# 433.net
KiCad netlist of a schematic drawn in EasyEDA Pro
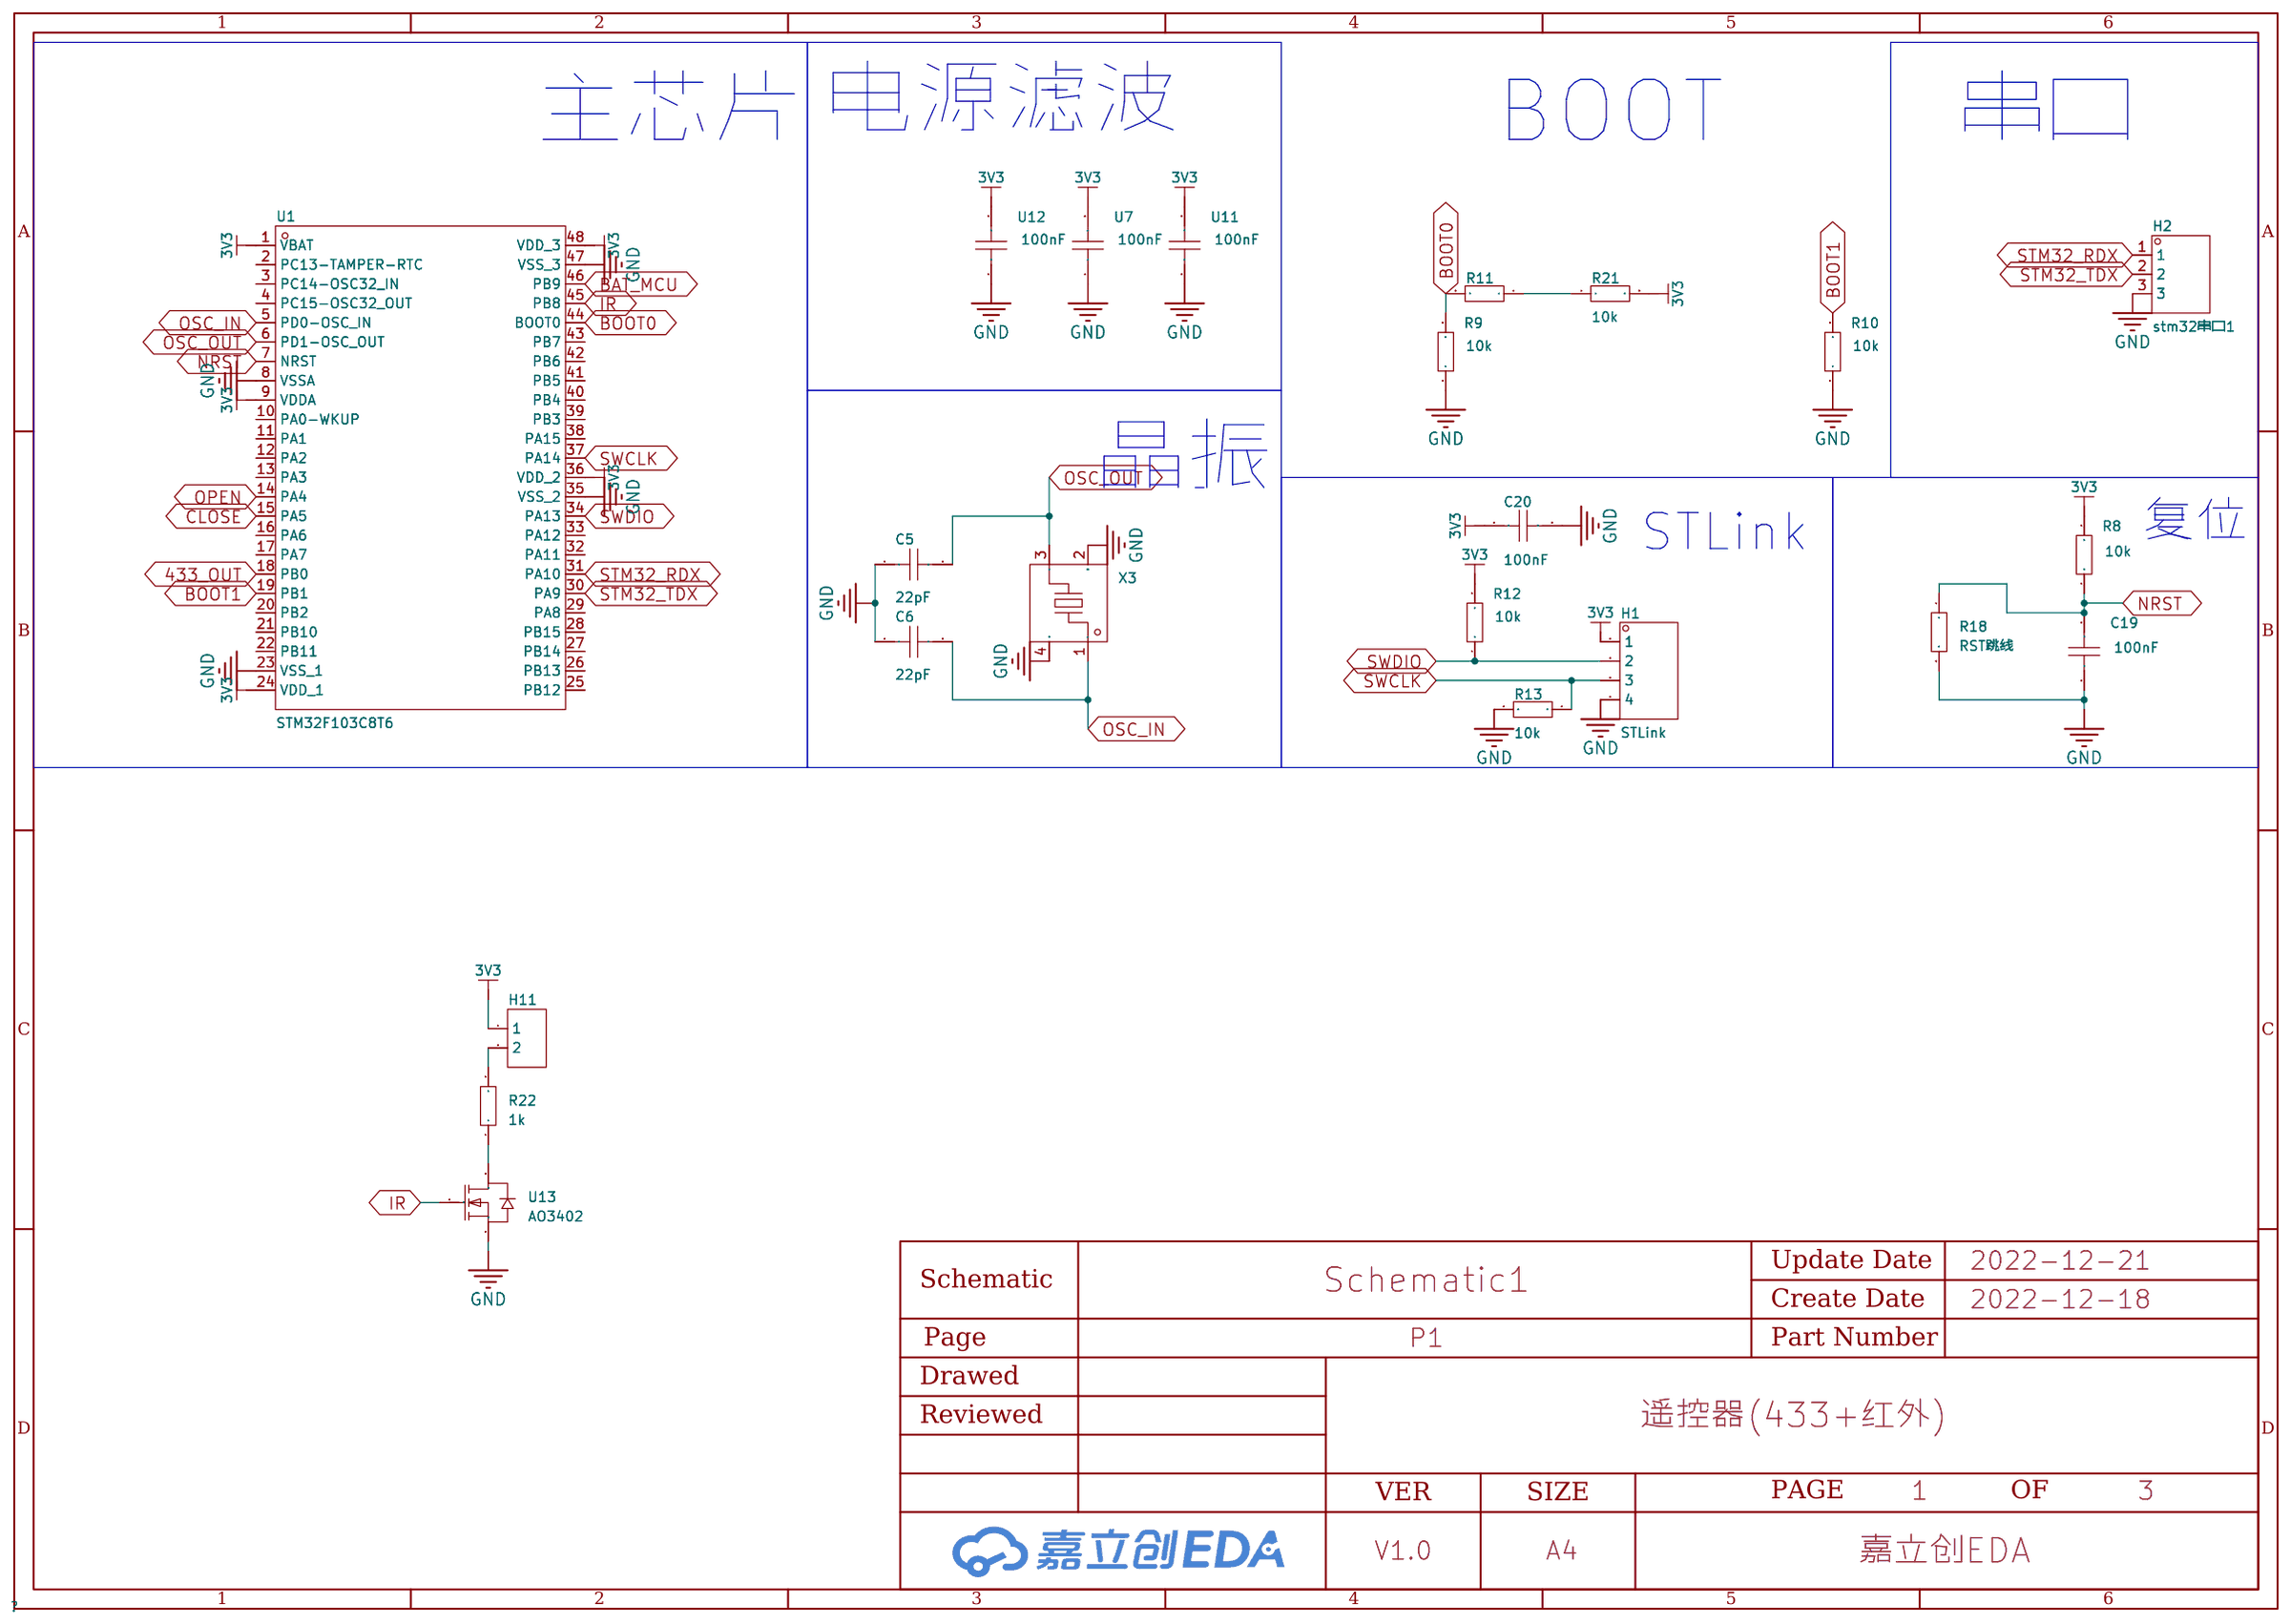
[diagram p0: P1]
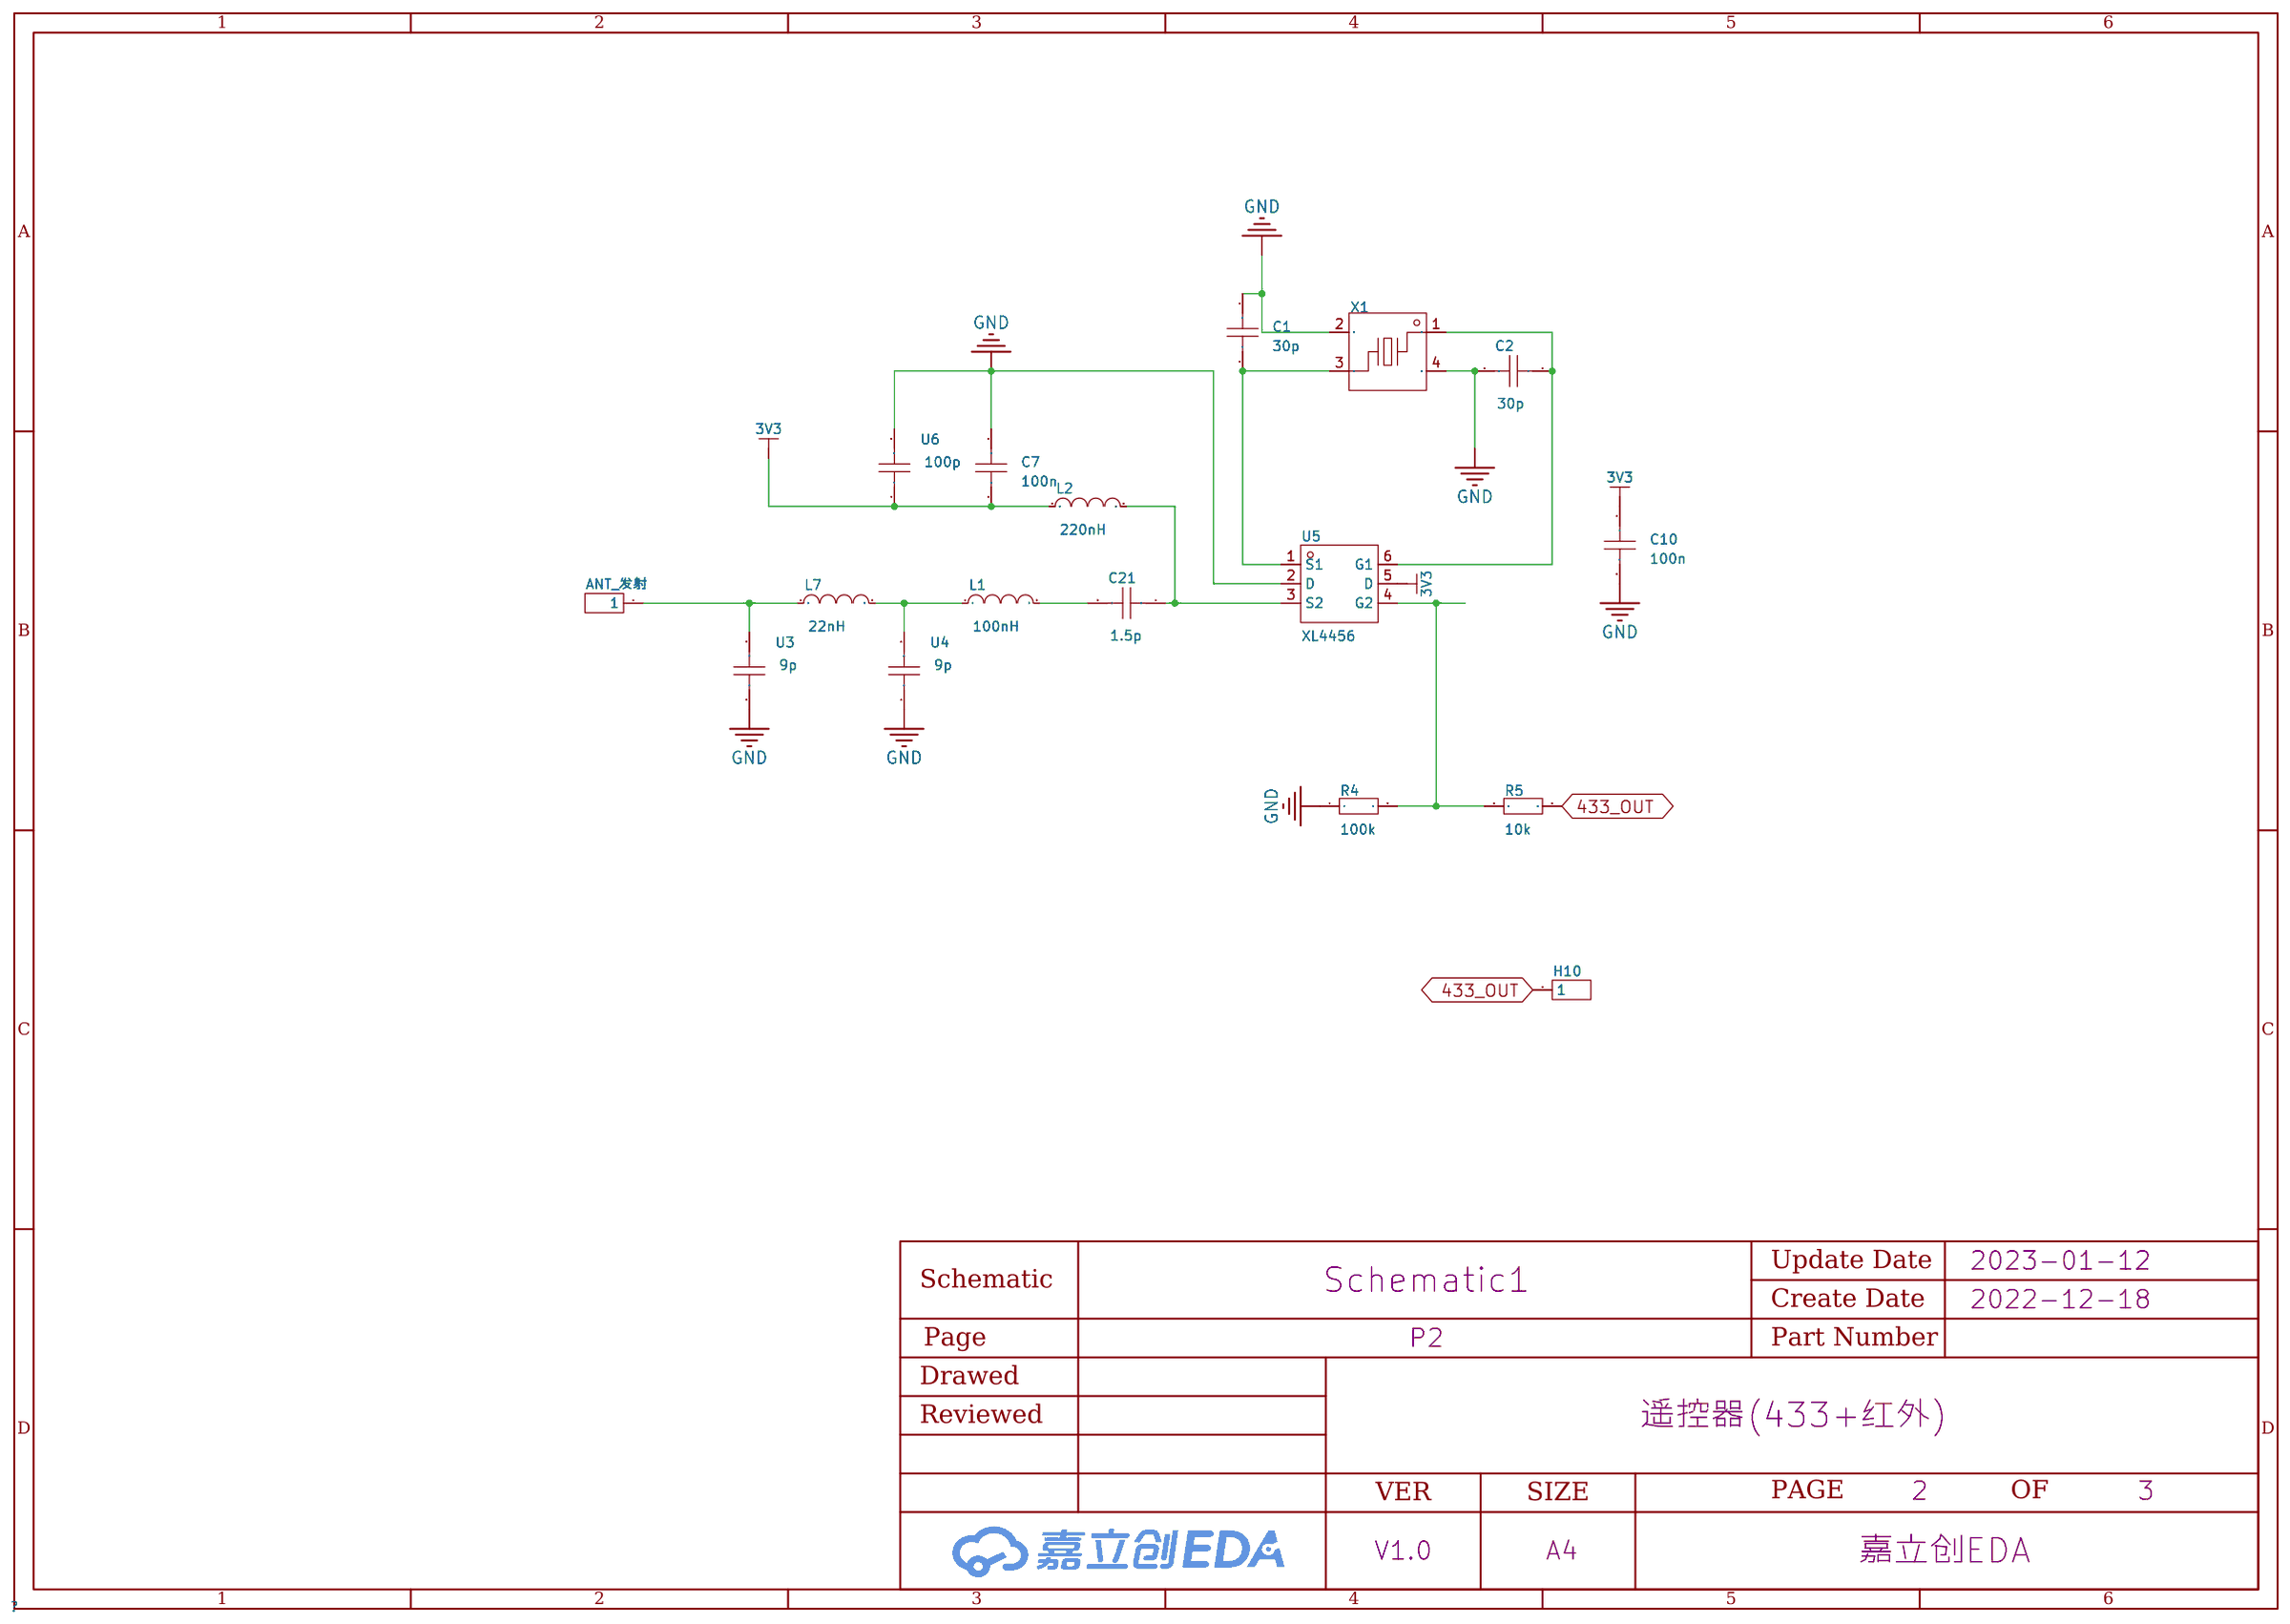
[diagram p1: P2]
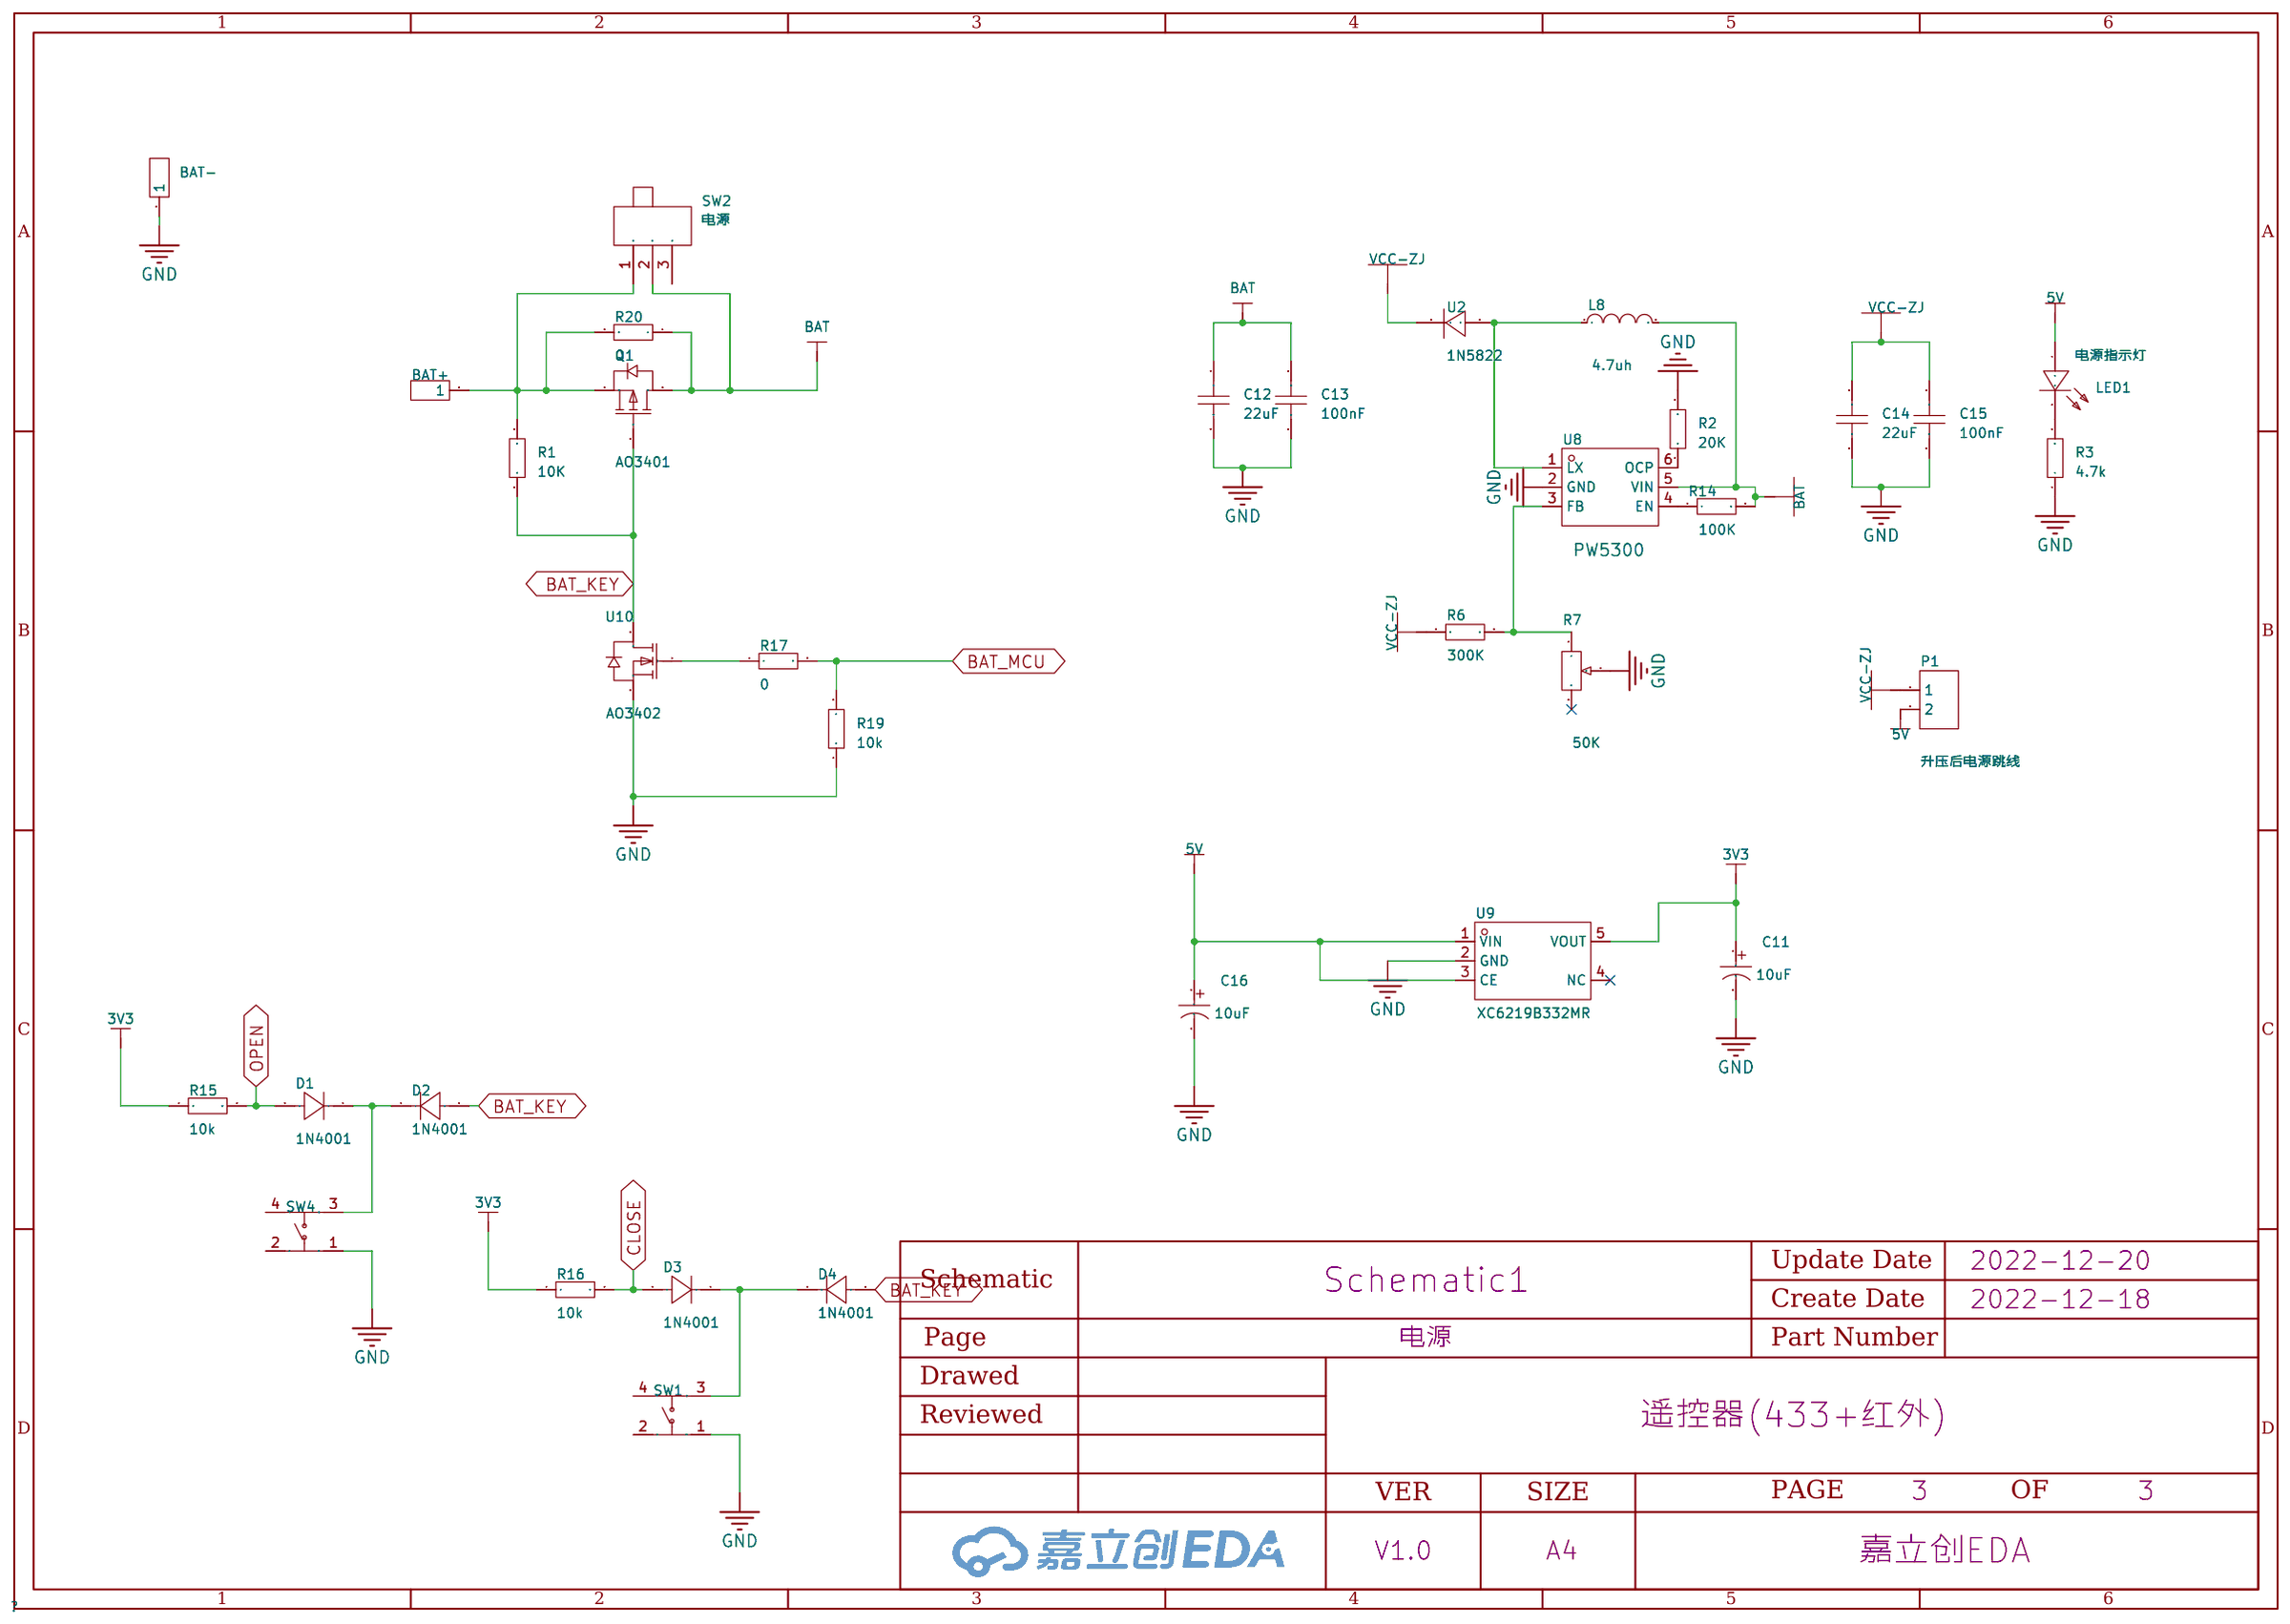
[diagram p2: 电源]

(export (version "E")
  (design (tool "Eeschema 10.0.6"))
  (components
    (comp (ref "C5")
      (value "22pF")
      (footprint "easyedapro:C0805")
      (fields (field (name "Manufacturer Part") "0805"))
      (libsource (lib "easyedapro") (part "0805_C9900012713"))
    )
    (comp (ref "C6")
      (value "22pF")
      (footprint "easyedapro:C0805")
      (fields (field (name "Manufacturer Part") "0805"))
      (libsource (lib "easyedapro") (part "0805_C9900012713"))
    )
    (comp (ref "C19")
      (value "100nF")
      (footprint "easyedapro:C0805")
      (fields (field (name "Manufacturer Part") "0805"))
      (libsource (lib "easyedapro") (part "0805_C9900012713"))
    )
    (comp (ref "C20")
      (value "100nF")
      (footprint "easyedapro:C0805")
      (fields (field (name "Manufacturer Part") "0805"))
      (libsource (lib "easyedapro") (part "0805_C9900012713"))
    )
    (comp (ref "H1")
      (value "STLink")
      (footprint "easyedapro:HDR-TH_4P-P2.54-V-M")
      (fields (field (name "Manufacturer Part") "B-2100S04P-A110") (field (name "Manufacturer") "Ckmtw(灿科盟)"))
      (libsource (lib "easyedapro") (part "Header-Male-2.54_1x4"))
    )
    (comp (ref "H2")
      (value "stm32串口1")
      (footprint "easyedapro:HDR-TH_3P-P2.54-V-M-1")
      (fields (field (name "Manufacturer Part") "77311-102-03LF") (field (name "Manufacturer") "Amphenol"))
      (libsource (lib "easyedapro") (part "77311-102-03LF"))
    )
    (comp (ref "H11")
      (value "~")
      (footprint "easyedapro:HDR-TH_2P-P2.54-V-F")
      (libsource (lib "easyedapro") (part "Header-Female-2.54_1x2"))
    )
    (comp (ref "R8")
      (value "10k")
      (footprint "easyedapro:R0805")
      (fields (field (name "Manufacturer Part") "0805"))
      (libsource (lib "easyedapro") (part "0805"))
    )
    (comp (ref "R9")
      (value "10k")
      (footprint "easyedapro:R0805")
      (fields (field (name "Manufacturer Part") "0805"))
      (libsource (lib "easyedapro") (part "0805"))
    )
    (comp (ref "R10")
      (value "10k")
      (footprint "easyedapro:R0805")
      (fields (field (name "Manufacturer Part") "0805"))
      (libsource (lib "easyedapro") (part "0805"))
    )
    (comp (ref "R11")
      (value "boot0跳线")
      (footprint "easyedapro:R0805")
      (fields (field (name "Manufacturer Part") "0805"))
      (libsource (lib "easyedapro") (part "0805"))
    )
    (comp (ref "R12")
      (value "10k")
      (footprint "easyedapro:R0805")
      (fields (field (name "Manufacturer Part") "0805"))
      (libsource (lib "easyedapro") (part "0805"))
    )
    (comp (ref "R13")
      (value "10k")
      (footprint "easyedapro:R0805")
      (fields (field (name "Manufacturer Part") "0805"))
      (libsource (lib "easyedapro") (part "0805"))
    )
    (comp (ref "R18")
      (value "RST跳线")
      (footprint "easyedapro:R0805")
      (fields (field (name "Manufacturer Part") "0805"))
      (libsource (lib "easyedapro") (part "0805"))
    )
    (comp (ref "R21")
      (value "10k")
      (footprint "easyedapro:R0805")
      (fields (field (name "Manufacturer Part") "0805"))
      (libsource (lib "easyedapro") (part "0805"))
    )
    (comp (ref "R22")
      (value "1k")
      (footprint "easyedapro:R0805")
      (fields (field (name "Manufacturer Part") "0805"))
      (libsource (lib "easyedapro") (part "0805"))
    )
    (comp (ref "U1")
      (value "STM32F103C8T6")
      (footprint "easyedapro:LQFP-48_L7.0-W7.0-P0.50-LS9.0-BL")
      (description "CPU位数:32-Bit;ROM类型:FLASH;CPU内核:ARM® Cortex®-M3;主频（MAX):72MHz;工作电压:2V ~ 3.6V;")
      (fields (field (name "Manufacturer") "ST(意法半导体)"))
      (libsource (lib "easyedapro") (part "STM32F103C8T6"))
    )
    (comp (ref "U7")
      (value "100nF")
      (footprint "easyedapro:C0603")
      (fields (field (name "Manufacturer Part") "1nF-C0603"))
      (libsource (lib "easyedapro") (part "1NF-C0603"))
    )
    (comp (ref "U11")
      (value "100nF")
      (footprint "easyedapro:C0603")
      (fields (field (name "Manufacturer Part") "1nF-C0603"))
      (libsource (lib "easyedapro") (part "1NF-C0603"))
    )
    (comp (ref "U12")
      (value "100nF")
      (footprint "easyedapro:C0603")
      (fields (field (name "Manufacturer Part") "1nF-C0603"))
      (libsource (lib "easyedapro") (part "1NF-C0603"))
    )
    (comp (ref "U13")
      (value "AO3402")
      (footprint "easyedapro:SOT-23-3_L2.9-W1.3-P1.90-LS2.4-BR")
      (fields (field (name "Manufacturer") "BORN(伯恩半导体)"))
      (libsource (lib "easyedapro") (part "AO3402_C5148472"))
    )
    (comp (ref "X3")
      (value "NX3225SA-26MHz-STD-CSR-6")
      (footprint "easyedapro:CRYSTAL-SMD_4P-L3.2-W2.5-BL")
      (fields (field (name "Manufacturer") "NDK"))
      (libsource (lib "easyedapro") (part "NX3225SA-26MHZ-STD-CSR-6"))
    )
    (comp (ref "ANT_发射")
      (value "~")
      (footprint "easyedapro:HDR-TH_1P-V-M_XKB_X4611WV-01I-C28D40")
      (libsource (lib "easyedapro") (part "HDR_1x1"))
    )
    (comp (ref "C1")
      (value "30p")
      (fields (field (name "Manufacturer Part") "0805"))
      (libsource (lib "easyedapro") (part "0805_C9900012713"))
    )
    (comp (ref "C2")
      (value "30p")
      (fields (field (name "Manufacturer Part") "0805"))
      (libsource (lib "easyedapro") (part "0805_C9900012713"))
    )
    (comp (ref "C7")
      (value "100n")
      (fields (field (name "Manufacturer Part") "0805"))
      (libsource (lib "easyedapro") (part "0805_C9900012713"))
    )
    (comp (ref "C10")
      (value "100n")
      (fields (field (name "Manufacturer Part") "0805"))
      (libsource (lib "easyedapro") (part "0805_C9900012713"))
    )
    (comp (ref "C21")
      (value "1.5p")
      (fields (field (name "Manufacturer Part") "0805"))
      (libsource (lib "easyedapro") (part "0805_C9900012713"))
    )
    (comp (ref "H10")
      (value "~")
      (footprint "easyedapro:HDR-TH_1P-V-M_XKB_X4611WV-01I-C28D40")
      (libsource (lib "easyedapro") (part "HDR_1x1"))
    )
    (comp (ref "L1")
      (value "100nH")
      (footprint "easyedapro:IND-SMD_L1.7-W1.0-SCW1608C39NJST")
      (fields (field (name "Manufacturer Part") "L0603"))
      (libsource (lib "easyedapro") (part "L0603_C9900016892"))
    )
    (comp (ref "L2")
      (value "220nH")
      (footprint "easyedapro:IND-SMD_L1.7-W1.0-SCW1608C39NJST")
      (fields (field (name "Manufacturer Part") "L0603"))
      (libsource (lib "easyedapro") (part "L0603_C9900016892"))
    )
    (comp (ref "L7")
      (value "22nH")
      (footprint "easyedapro:IND-SMD_L1.7-W1.0-SCW1608C39NJST")
      (fields (field (name "Manufacturer Part") "L0603"))
      (libsource (lib "easyedapro") (part "L0603_C9900016892"))
    )
    (comp (ref "R4")
      (value "100k")
      (footprint "easyedapro:R0805")
      (fields (field (name "Manufacturer Part") "0805"))
      (libsource (lib "easyedapro") (part "0805"))
    )
    (comp (ref "R5")
      (value "10k")
      (footprint "easyedapro:R0805")
      (fields (field (name "Manufacturer Part") "0805"))
      (libsource (lib "easyedapro") (part "0805"))
    )
    (comp (ref "U3")
      (value "9p")
      (footprint "easyedapro:C0603")
      (fields (field (name "Manufacturer Part") "104P"))
      (libsource (lib "easyedapro") (part "104P"))
    )
    (comp (ref "U4")
      (value "9p")
      (footprint "easyedapro:C0603")
      (fields (field (name "Manufacturer Part") "104P"))
      (libsource (lib "easyedapro") (part "104P"))
    )
    (comp (ref "U5")
      (value "XL4456")
      (footprint "easyedapro:SOT-23-6_L2.9-W1.6-P0.95-LS2.9-BL")
      (fields (field (name "Manufacturer Part") "JMTM8205A") (field (name "Manufacturer") "JJW(捷捷微)"))
      (libsource (lib "easyedapro") (part "JMTM8205A"))
    )
    (comp (ref "U6")
      (value "100p")
      (footprint "easyedapro:C0603")
      (fields (field (name "Manufacturer Part") "104P"))
      (libsource (lib "easyedapro") (part "104P"))
    )
    (comp (ref "X1")
      (value "NX3225SA-26MHz-STD-CSR-6")
      (footprint "easyedapro:CRYSTAL-SMD_4P-L3.2-W2.5-BL")
      (fields (field (name "Manufacturer") "NDK"))
      (libsource (lib "easyedapro") (part "NX3225SA-26MHZ-STD-CSR-6"))
    )
    (comp (ref "BAT+")
      (value "~")
      (footprint "easyedapro:HDR-TH_1P-P2.54-V-M")
      (description "间距:-;总PIN位数:1;排数:1;插针结构:-;行距:-;安装类型:直插;圆针/方针:-;额定电流:-;额定电压:-;配合针长度:-;塑高:-;触头材质:-;触头镀层:-;颜色:黑色;")
      (fields (field (name "Manufacturer Part") "2.54-1*1P针") (field (name "Manufacturer") "BOOMELE(博穆精密)"))
      (libsource (lib "easyedapro") (part "Header-Male-2.54_1x1"))
    )
    (comp (ref "BAT-")
      (value "~")
      (footprint "easyedapro:HDR-TH_1P-P2.54-V-M")
      (description "间距:-;总PIN位数:1;排数:1;插针结构:-;行距:-;安装类型:直插;圆针/方针:-;额定电流:-;额定电压:-;配合针长度:-;塑高:-;触头材质:-;触头镀层:-;颜色:黑色;")
      (fields (field (name "Manufacturer Part") "2.54-1*1P针") (field (name "Manufacturer") "BOOMELE(博穆精密)"))
      (libsource (lib "easyedapro") (part "Header-Male-2.54_1x1"))
    )
    (comp (ref "C11")
      (value "10uF")
      (footprint "easyedapro:CAP-TH_BD5.0-P2.00-D0.8-FD")
      (fields
        (field (name "Manufacturer Part") "KM106M025D11RR0VH2FP0")
        (field (name "Manufacturer") "CX(承兴)")
      )
      (libsource (lib "easyedapro") (part "10uF 25V 5*11"))
    )
    (comp (ref "C12")
      (value "22uF")
      (footprint "easyedapro:C0805")
      (fields (field (name "Manufacturer Part") "0805"))
      (libsource (lib "easyedapro") (part "0805_C9900012713"))
    )
    (comp (ref "C13")
      (value "100nF")
      (footprint "easyedapro:C0805")
      (fields (field (name "Manufacturer Part") "0805"))
      (libsource (lib "easyedapro") (part "0805_C9900012713"))
    )
    (comp (ref "C14")
      (value "22uF")
      (footprint "easyedapro:C0805")
      (fields (field (name "Manufacturer Part") "0805"))
      (libsource (lib "easyedapro") (part "0805_C9900012713"))
    )
    (comp (ref "C15")
      (value "100nF")
      (footprint "easyedapro:C0805")
      (fields (field (name "Manufacturer Part") "0805"))
      (libsource (lib "easyedapro") (part "0805_C9900012713"))
    )
    (comp (ref "C16")
      (value "10uF")
      (footprint "easyedapro:CAP-TH_BD5.0-P2.00-D0.8-FD")
      (fields
        (field (name "Manufacturer Part") "KM106M025D11RR0VH2FP0")
        (field (name "Manufacturer") "CX(承兴)")
      )
      (libsource (lib "easyedapro") (part "10uF 25V 5*11"))
    )
    (comp (ref "D1")
      (value "1N4001")
      (footprint "easyedapro:SMA_L4.2-W2.6-LS5.0-RD")
      (description "二极管配置:独立式;直流反向耐压(Vr):50V;平均整流电流(Io):1A;正向压降(Vf):1.1V@1A;反向电流(Ir):5uA@50V;")
      (fields (field (name "Manufacturer") "YONGYUTAI(永裕泰)"))
      (libsource (lib "easyedapro") (part "1N4001_C2909965"))
    )
    (comp (ref "D2")
      (value "1N4001")
      (footprint "easyedapro:SMA_L4.2-W2.6-LS5.0-RD")
      (description "二极管配置:独立式;直流反向耐压(Vr):50V;平均整流电流(Io):1A;正向压降(Vf):1.1V@1A;反向电流(Ir):5uA@50V;")
      (fields (field (name "Manufacturer") "YONGYUTAI(永裕泰)"))
      (libsource (lib "easyedapro") (part "1N4001_C2909965"))
    )
    (comp (ref "D3")
      (value "1N4001")
      (footprint "easyedapro:SMA_L4.2-W2.6-LS5.0-RD")
      (description "二极管配置:独立式;直流反向耐压(Vr):50V;平均整流电流(Io):1A;正向压降(Vf):1.1V@1A;反向电流(Ir):5uA@50V;")
      (fields (field (name "Manufacturer") "YONGYUTAI(永裕泰)"))
      (libsource (lib "easyedapro") (part "1N4001_C2909965"))
    )
    (comp (ref "D4")
      (value "1N4001")
      (footprint "easyedapro:SMA_L4.2-W2.6-LS5.0-RD")
      (description "二极管配置:独立式;直流反向耐压(Vr):50V;平均整流电流(Io):1A;正向压降(Vf):1.1V@1A;反向电流(Ir):5uA@50V;")
      (fields (field (name "Manufacturer") "YONGYUTAI(永裕泰)"))
      (libsource (lib "easyedapro") (part "1N4001_C2909965"))
    )
    (comp (ref "L8")
      (value "1uH")
      (footprint "easyedapro:IND-SMD_L4.0-W4.0")
      (description "电感值:1uH;精度:±30%;额定电流:2.15A;直流电阻(DCR):29mΩ;")
      (fields (field (name "Manufacturer Part") "YNR4020-1R0N") (field (name "Manufacturer") "YJYCOIN(益嘉源)"))
      (libsource (lib "easyedapro") (part "YNR4020-1R0N"))
    )
    (comp (ref "LED1")
      (value "电源指示灯")
      (footprint "easyedapro:LED0805-R-RD")
      (description "发光颜色:翠绿;")
      (fields (field (name "Manufacturer Part") "NCD0805G1") (field (name "Manufacturer") "国星光电"))
      (libsource (lib "easyedapro") (part "FC-2012UGK-520D5"))
    )
    (comp (ref "P1")
      (value "升压后电源跳线")
      (footprint "easyedapro:HDR-TH_2P-P2.54-V-F")
      (description "间距:2.54mm;总孔位数:2;排数:1;插孔结构:1x2P;行距:-;安装类型:直插;塑高:-;触头材质:-;触头镀层:-;")
      (fields (field (name "Manufacturer Part") "2.54-1*2P母") (field (name "Manufacturer") "BOOMELE(博穆精密)"))
      (libsource (lib "easyedapro") (part "Header-Female-2.54_1x2"))
    )
    (comp (ref "Q1")
      (value "AO3401")
      (footprint "easyedapro:SOT-23-3_L2.9-W1.6-P1.90-LS2.8-BR")
      (fields (field (name "Manufacturer") "LGE(鲁光)"))
      (libsource (lib "easyedapro") (part "AO3401_C688915"))
    )
    (comp (ref "R1")
      (value "10K")
      (footprint "easyedapro:R0805")
      (fields (field (name "Manufacturer Part") "0805"))
      (libsource (lib "easyedapro") (part "0805"))
    )
    (comp (ref "R2")
      (value "20K")
      (footprint "easyedapro:R0805")
      (fields (field (name "Manufacturer Part") "0805"))
      (libsource (lib "easyedapro") (part "0805"))
    )
    (comp (ref "R3")
      (value "4.7k")
      (footprint "easyedapro:R0805")
      (fields (field (name "Manufacturer Part") "0805"))
      (libsource (lib "easyedapro") (part "0805"))
    )
    (comp (ref "R6")
      (value "300K")
      (footprint "easyedapro:R0805")
      (fields (field (name "Manufacturer Part") "0805"))
      (libsource (lib "easyedapro") (part "0805"))
    )
    (comp (ref "R7")
      (value "50K")
      (footprint "easyedapro:RES-ADJ-TH_3P_L9.6-W4.8-P2.50-L")
      (fields (field (name "Manufacturer Part") "CT-94EW101") (field (name "Manufacturer") "NIDEC(尼得科)"))
      (libsource (lib "easyedapro") (part "CT-94EW101"))
    )
    (comp (ref "R14")
      (value "100K")
      (footprint "easyedapro:R0805")
      (fields (field (name "Manufacturer Part") "0805"))
      (libsource (lib "easyedapro") (part "0805"))
    )
    (comp (ref "R15")
      (value "10k")
      (footprint "easyedapro:R0805")
      (fields (field (name "Manufacturer Part") "0805"))
      (libsource (lib "easyedapro") (part "0805"))
    )
    (comp (ref "R16")
      (value "10k")
      (footprint "easyedapro:R0805")
      (fields (field (name "Manufacturer Part") "0805"))
      (libsource (lib "easyedapro") (part "0805"))
    )
    (comp (ref "R17")
      (value "0")
      (footprint "easyedapro:R0805")
      (fields (field (name "Manufacturer Part") "0805"))
      (libsource (lib "easyedapro") (part "0805"))
    )
    (comp (ref "R19")
      (value "10k")
      (footprint "easyedapro:R0805")
      (fields (field (name "Manufacturer Part") "0805"))
      (libsource (lib "easyedapro") (part "0805"))
    )
    (comp (ref "R20")
      (value "0")
      (footprint "easyedapro:R0805")
      (fields (field (name "Manufacturer Part") "0805"))
      (libsource (lib "easyedapro") (part "0805"))
    )
    (comp (ref "SW1")
      (value "MPU6050")
      (footprint "easyedapro:SW-SMD_4P-L6.0-W6.0-P4.50-LS9.0-2")
      (fields
        (field (name "Manufacturer Part") "KH-6X6X5H-STM")
        (field (name "Manufacturer") "kinghelm(金航标)")
      )
      (libsource (lib "easyedapro") (part "KH-6X6X5H-STM"))
    )
    (comp (ref "SW2")
      (value "电源")
      (footprint "easyedapro:SW-TH_MK-12D18-G040")
      (fields (field (name "Manufacturer Part") "MK-12D18-G020") (field (name "Manufacturer") "G-Switch(品赞)"))
      (libsource (lib "easyedapro") (part "MK-12D18-G020"))
    )
    (comp (ref "SW4")
      (value "MPU6050")
      (footprint "easyedapro:SW-SMD_4P-L6.0-W6.0-P4.50-LS9.0-2")
      (fields
        (field (name "Manufacturer Part") "KH-6X6X5H-STM")
        (field (name "Manufacturer") "kinghelm(金航标)")
      )
      (libsource (lib "easyedapro") (part "KH-6X6X5H-STM"))
    )
    (comp (ref "U2")
      (value "1N5822")
      (footprint "easyedapro:SMA_L4.3-W2.5-LS5.0-FD")
      (fields (field (name "Manufacturer Part") "SMAJ12ASMA"))
      (libsource (lib "easyedapro") (part "SMAJ12ASMA"))
    )
    (comp (ref "U8")
      (value "PW5300")
      (footprint "easyedapro:SOT-23-6_L2.9-W1.6-P0.95-LS2.8-BL")
      (libsource (lib "easyedapro") (part "PW5300"))
    )
    (comp (ref "U9")
      (value "XC6219B332MR")
      (footprint "easyedapro:SOT-23-5_L2.9-W1.6-P0.95-LS2.8-BR")
      (fields (field (name "Manufacturer") "TECH PUBLIC(台舟)"))
      (libsource (lib "easyedapro") (part "XC6219B332MR_C2940621"))
    )
    (comp (ref "U10")
      (value "AO3402")
      (footprint "easyedapro:SOT-23-3_L2.9-W1.3-P1.90-LS2.4-BR")
      (fields (field (name "Manufacturer") "BORN(伯恩半导体)"))
      (libsource (lib "easyedapro") (part "AO3402_C5148472"))
    )
  )
  (nets
    (net (code "1") (name "3V3") (class "Default")
      (node (ref "C10") (pin "1") (pinfunction "1_1") (pintype "input"))
      (node (ref "C11") (pin "1") (pinfunction "1_1") (pintype "input"))
      (node (ref "C20") (pin "1") (pinfunction "1_1") (pintype "input"))
      (node (ref "C7") (pin "2") (pinfunction "2_2") (pintype "input"))
      (node (ref "H1") (pin "1") (pinfunction "1_1") (pintype "input"))
      (node (ref "H11") (pin "1") (pinfunction "1_1") (pintype "input"))
      (node (ref "L2") (pin "1") (pinfunction "1_1") (pintype "input"))
      (node (ref "R12") (pin "2") (pinfunction "2_2") (pintype "input"))
      (node (ref "R15") (pin "1") (pinfunction "1_1") (pintype "input"))
      (node (ref "R16") (pin "1") (pinfunction "1_1") (pintype "input"))
      (node (ref "R21") (pin "2") (pinfunction "2_2") (pintype "input"))
      (node (ref "R8") (pin "2") (pinfunction "2_2") (pintype "input"))
      (node (ref "U1") (pin "1") (pinfunction "VBAT_1") (pintype "input"))
      (node (ref "U1") (pin "24") (pinfunction "VDD_1_24") (pintype "input"))
      (node (ref "U1") (pin "36") (pinfunction "VDD_2_36") (pintype "input"))
      (node (ref "U1") (pin "48") (pinfunction "VDD_3_48") (pintype "input"))
      (node (ref "U1") (pin "9") (pinfunction "VDDA_9") (pintype "input"))
      (node (ref "U11") (pin "2") (pinfunction "2_2") (pintype "input"))
      (node (ref "U12") (pin "2") (pinfunction "2_2") (pintype "input"))
      (node (ref "U5") (pin "5") (pinfunction "D_5") (pintype "input"))
      (node (ref "U6") (pin "1") (pinfunction "1_1") (pintype "input"))
      (node (ref "U7") (pin "2") (pinfunction "2_2") (pintype "input"))
      (node (ref "U9") (pin "5") (pinfunction "VOUT_5") (pintype "input"))
    )
    (net (code "2") (name "5V") (class "Default")
      (node (ref "C16") (pin "1") (pinfunction "1_1") (pintype "input"))
      (node (ref "LED1") (pin "1") (pinfunction "A_1") (pintype "input"))
      (node (ref "P1") (pin "2") (pinfunction "2_2") (pintype "input"))
      (node (ref "U9") (pin "1") (pinfunction "VIN_1") (pintype "input"))
      (node (ref "U9") (pin "3") (pinfunction "CE_3") (pintype "input"))
    )
    (net (code "3") (name "433_OUT") (class "Default")
      (node (ref "H10") (pin "1") (pinfunction "1_1") (pintype "unspecified"))
      (node (ref "R5") (pin "2") (pinfunction "2_2") (pintype "input"))
      (node (ref "U1") (pin "18") (pinfunction "PB0_18") (pintype "input"))
    )
    (net (code "4") (name "BAT") (class "Default")
      (node (ref "C12") (pin "1") (pinfunction "1_1") (pintype "input"))
      (node (ref "C13") (pin "1") (pinfunction "1_1") (pintype "input"))
      (node (ref "L8") (pin "2") (pinfunction "2_2") (pintype "input"))
      (node (ref "Q1") (pin "3") (pinfunction "D_3") (pintype "input"))
      (node (ref "R14") (pin "2") (pinfunction "2_2") (pintype "input"))
      (node (ref "R20") (pin "1") (pinfunction "1_1") (pintype "input"))
      (node (ref "SW2") (pin "2") (pinfunction "2_2") (pintype "input"))
      (node (ref "U8") (pin "5") (pinfunction "VIN_5") (pintype "input"))
    )
    (net (code "5") (name "BAT_KEY") (class "Default")
      (node (ref "D2") (pin "2") (pinfunction "A_2") (pintype "input"))
      (node (ref "D4") (pin "2") (pinfunction "A_2") (pintype "input"))
      (node (ref "Q1") (pin "1") (pinfunction "G_1") (pintype "input"))
      (node (ref "R1") (pin "2") (pinfunction "2_2") (pintype "input"))
      (node (ref "U10") (pin "3") (pinfunction "D_3") (pintype "input"))
    )
    (net (code "6") (name "BAT_MCU") (class "Default")
      (node (ref "R17") (pin "2") (pinfunction "2_2") (pintype "input"))
      (node (ref "R19") (pin "2") (pinfunction "2_2") (pintype "input"))
      (node (ref "U1") (pin "46") (pinfunction "PB9_46") (pintype "input"))
    )
    (net (code "7") (name "BOOT0") (class "Default")
      (node (ref "R11") (pin "2") (pinfunction "2_2") (pintype "input"))
      (node (ref "R9") (pin "2") (pinfunction "2_2") (pintype "input"))
      (node (ref "U1") (pin "44") (pinfunction "BOOT0_44") (pintype "input"))
    )
    (net (code "8") (name "BOOT1") (class "Default")
      (node (ref "R10") (pin "2") (pinfunction "2_2") (pintype "input"))
      (node (ref "U1") (pin "19") (pinfunction "PB1_19") (pintype "input"))
    )
    (net (code "9") (name "CLOSE") (class "Default")
      (node (ref "D3") (pin "2") (pinfunction "A_2") (pintype "input"))
      (node (ref "R16") (pin "2") (pinfunction "2_2") (pintype "input"))
      (node (ref "U1") (pin "15") (pinfunction "PA5_15") (pintype "input"))
    )
    (net (code "10") (name "GND") (class "Default")
      (node (ref "BAT-") (pin "1") (pinfunction "1_1") (pintype "input"))
      (node (ref "C1") (pin "1") (pinfunction "1_1") (pintype "input"))
      (node (ref "C10") (pin "2") (pinfunction "2_2") (pintype "input"))
      (node (ref "C11") (pin "2") (pinfunction "2_2") (pintype "input"))
      (node (ref "C12") (pin "2") (pinfunction "2_2") (pintype "input"))
      (node (ref "C13") (pin "2") (pinfunction "2_2") (pintype "input"))
      (node (ref "C14") (pin "2") (pinfunction "2_2") (pintype "input"))
      (node (ref "C15") (pin "2") (pinfunction "2_2") (pintype "input"))
      (node (ref "C16") (pin "2") (pinfunction "2_2") (pintype "input"))
      (node (ref "C19") (pin "2") (pinfunction "2_2") (pintype "input"))
      (node (ref "C2") (pin "2") (pinfunction "2_2") (pintype "input"))
      (node (ref "C20") (pin "2") (pinfunction "2_2") (pintype "input"))
      (node (ref "C5") (pin "1") (pinfunction "1_1") (pintype "input"))
      (node (ref "C6") (pin "1") (pinfunction "1_1") (pintype "input"))
      (node (ref "C7") (pin "1") (pinfunction "1_1") (pintype "input"))
      (node (ref "H1") (pin "4") (pinfunction "4_4") (pintype "input"))
      (node (ref "H2") (pin "3") (pinfunction "3_3") (pintype "input"))
      (node (ref "R10") (pin "1") (pinfunction "1_1") (pintype "input"))
      (node (ref "R13") (pin "2") (pinfunction "2_2") (pintype "input"))
      (node (ref "R18") (pin "2") (pinfunction "2_2") (pintype "input"))
      (node (ref "R19") (pin "1") (pinfunction "1_1") (pintype "input"))
      (node (ref "R2") (pin "2") (pinfunction "2_2") (pintype "input"))
      (node (ref "R3") (pin "1") (pinfunction "1_1") (pintype "input"))
      (node (ref "R4") (pin "1") (pinfunction "1_1") (pintype "input"))
      (node (ref "R7") (pin "2") (pinfunction "2_2") (pintype "input"))
      (node (ref "R9") (pin "1") (pinfunction "1_1") (pintype "input"))
      (node (ref "SW1") (pin "1") (pinfunction "1_1") (pintype "input"))
      (node (ref "SW4") (pin "1") (pinfunction "1_1") (pintype "input"))
      (node (ref "U1") (pin "23") (pinfunction "VSS_1_23") (pintype "input"))
      (node (ref "U1") (pin "35") (pinfunction "VSS_2_35") (pintype "input"))
      (node (ref "U1") (pin "47") (pinfunction "VSS_3_47") (pintype "input"))
      (node (ref "U1") (pin "8") (pinfunction "VSSA_8") (pintype "input"))
      (node (ref "U10") (pin "2") (pinfunction "S_2") (pintype "input"))
      (node (ref "U11") (pin "1") (pinfunction "1_1") (pintype "input"))
      (node (ref "U12") (pin "1") (pinfunction "1_1") (pintype "input"))
      (node (ref "U13") (pin "2") (pinfunction "S_2") (pintype "input"))
      (node (ref "U3") (pin "1") (pinfunction "1_1") (pintype "input"))
      (node (ref "U4") (pin "1") (pinfunction "1_1") (pintype "input"))
      (node (ref "U5") (pin "2") (pinfunction "D_2") (pintype "input"))
      (node (ref "U6") (pin "2") (pinfunction "2_2") (pintype "input"))
      (node (ref "U7") (pin "1") (pinfunction "1_1") (pintype "input"))
      (node (ref "U8") (pin "2") (pinfunction "GND_2") (pintype "input"))
      (node (ref "U9") (pin "2") (pinfunction "GND_2") (pintype "input"))
      (node (ref "X1") (pin "2") (pinfunction "GND_2") (pintype "input"))
      (node (ref "X1") (pin "4") (pinfunction "GND_4") (pintype "input"))
      (node (ref "X3") (pin "2") (pinfunction "GND_2") (pintype "input"))
      (node (ref "X3") (pin "4") (pinfunction "GND_4") (pintype "input"))
    )
    (net (code "11") (name "IR") (class "Default")
      (node (ref "U1") (pin "45") (pinfunction "PB8_45") (pintype "input"))
      (node (ref "U13") (pin "1") (pinfunction "G_1") (pintype "input"))
    )
    (net (code "12") (name "NRST") (class "Default")
      (node (ref "C19") (pin "1") (pinfunction "1_1") (pintype "input"))
      (node (ref "R18") (pin "1") (pinfunction "1_1") (pintype "input"))
      (node (ref "R8") (pin "1") (pinfunction "1_1") (pintype "input"))
      (node (ref "U1") (pin "7") (pinfunction "NRST_7") (pintype "input"))
    )
    (net (code "13") (name "Net-(ANT_发射-Pad1)") (class "Default")
      (node (ref "ANT_发射") (pin "1") (pinfunction "1_1") (pintype "unspecified"))
      (node (ref "L7") (pin "1") (pinfunction "1_1") (pintype "input"))
      (node (ref "U3") (pin "2") (pinfunction "2_2") (pintype "input"))
    )
    (net (code "14") (name "Net-(C21-Pad2)") (class "Default")
      (node (ref "C21") (pin "2") (pinfunction "2_2") (pintype "input"))
      (node (ref "L1") (pin "2") (pinfunction "2_2") (pintype "input"))
    )
    (net (code "15") (name "Net-(D1-K)") (class "Default")
      (node (ref "D1") (pin "1") (pinfunction "K_1") (pintype "input"))
      (node (ref "D2") (pin "1") (pinfunction "K_1") (pintype "input"))
      (node (ref "SW4") (pin "3") (pinfunction "3_3") (pintype "input"))
    )
    (net (code "16") (name "Net-(D3-K)") (class "Default")
      (node (ref "D3") (pin "1") (pinfunction "K_1") (pintype "input"))
      (node (ref "D4") (pin "1") (pinfunction "K_1") (pintype "input"))
      (node (ref "SW1") (pin "3") (pinfunction "3_3") (pintype "input"))
    )
    (net (code "17") (name "Net-(H11-Pad2)") (class "Default")
      (node (ref "H11") (pin "2") (pinfunction "2_2") (pintype "input"))
      (node (ref "R22") (pin "2") (pinfunction "2_2") (pintype "input"))
    )
    (net (code "18") (name "Net-(L1-Pad1)") (class "Default")
      (node (ref "L1") (pin "1") (pinfunction "1_1") (pintype "input"))
      (node (ref "L7") (pin "2") (pinfunction "2_2") (pintype "input"))
      (node (ref "U4") (pin "2") (pinfunction "2_2") (pintype "input"))
    )
    (net (code "19") (name "Net-(LED1-K)") (class "Default")
      (node (ref "LED1") (pin "2") (pinfunction "K_2") (pintype "input"))
      (node (ref "R3") (pin "2") (pinfunction "2_2") (pintype "input"))
    )
    (net (code "20") (name "Net-(Q1-S)") (class "Default")
      (node (ref "BAT+") (pin "1") (pinfunction "1_1") (pintype "input"))
      (node (ref "Q1") (pin "2") (pinfunction "S_2") (pintype "input"))
      (node (ref "R1") (pin "1") (pinfunction "1_1") (pintype "input"))
      (node (ref "R20") (pin "2") (pinfunction "2_2") (pintype "input"))
      (node (ref "SW2") (pin "1") (pinfunction "1_1") (pintype "input"))
    )
    (net (code "21") (name "Net-(R11-Pad1)") (class "Default")
      (node (ref "R11") (pin "1") (pinfunction "1_1") (pintype "input"))
      (node (ref "R21") (pin "1") (pinfunction "1_1") (pintype "input"))
    )
    (net (code "22") (name "Net-(U2-A)") (class "Default")
      (node (ref "L8") (pin "1") (pinfunction "1_1") (pintype "input"))
      (node (ref "U2") (pin "1") (pinfunction "A_1") (pintype "input"))
      (node (ref "U8") (pin "1") (pinfunction "LX_1") (pintype "input"))
    )
    (net (code "23") (name "Net-(U5-G1)") (class "Default")
      (node (ref "C2") (pin "1") (pinfunction "1_1") (pintype "input"))
      (node (ref "U5") (pin "6") (pinfunction "G1_6") (pintype "input"))
      (node (ref "X1") (pin "1") (pinfunction "1_1") (pintype "input"))
    )
    (net (code "24") (name "Net-(U5-G2)") (class "Default")
      (node (ref "R4") (pin "2") (pinfunction "2_2") (pintype "input"))
      (node (ref "R5") (pin "1") (pinfunction "1_1") (pintype "input"))
      (node (ref "U5") (pin "4") (pinfunction "G2_4") (pintype "input"))
    )
    (net (code "25") (name "Net-(U5-S1)") (class "Default")
      (node (ref "C1") (pin "2") (pinfunction "2_2") (pintype "input"))
      (node (ref "U5") (pin "1") (pinfunction "S1_1") (pintype "input"))
      (node (ref "X1") (pin "3") (pinfunction "3_3") (pintype "input"))
    )
    (net (code "26") (name "Net-(U5-S2)") (class "Default")
      (node (ref "C21") (pin "1") (pinfunction "1_1") (pintype "input"))
      (node (ref "L2") (pin "2") (pinfunction "2_2") (pintype "input"))
      (node (ref "U5") (pin "3") (pinfunction "S2_3") (pintype "input"))
    )
    (net (code "27") (name "Net-(U8-EN)") (class "Default")
      (node (ref "R14") (pin "1") (pinfunction "1_1") (pintype "input"))
      (node (ref "U8") (pin "4") (pinfunction "EN_4") (pintype "input"))
    )
    (net (code "28") (name "Net-(U8-FB)") (class "Default")
      (node (ref "R6") (pin "2") (pinfunction "2_2") (pintype "input"))
      (node (ref "R7") (pin "1") (pinfunction "1_1") (pintype "input"))
      (node (ref "U8") (pin "3") (pinfunction "FB_3") (pintype "input"))
    )
    (net (code "29") (name "Net-(U8-OCP)") (class "Default")
      (node (ref "R2") (pin "1") (pinfunction "1_1") (pintype "input"))
      (node (ref "U8") (pin "6") (pinfunction "OCP_6") (pintype "input"))
    )
    (net (code "30") (name "Net-(U10-G)") (class "Default")
      (node (ref "R17") (pin "1") (pinfunction "1_1") (pintype "input"))
      (node (ref "U10") (pin "1") (pinfunction "G_1") (pintype "input"))
    )
    (net (code "31") (name "Net-(U13-D)") (class "Default")
      (node (ref "R22") (pin "1") (pinfunction "1_1") (pintype "input"))
      (node (ref "U13") (pin "3") (pinfunction "D_3") (pintype "input"))
    )
    (net (code "32") (name "OPEN") (class "Default")
      (node (ref "D1") (pin "2") (pinfunction "A_2") (pintype "input"))
      (node (ref "R15") (pin "2") (pinfunction "2_2") (pintype "input"))
      (node (ref "U1") (pin "14") (pinfunction "PA4_14") (pintype "input"))
    )
    (net (code "33") (name "OSC_IN") (class "Default")
      (node (ref "C6") (pin "2") (pinfunction "2_2") (pintype "input"))
      (node (ref "U1") (pin "5") (pinfunction "PD0-OSC_IN_5") (pintype "input"))
      (node (ref "X3") (pin "1") (pinfunction "1_1") (pintype "input"))
    )
    (net (code "34") (name "OSC_OUT") (class "Default")
      (node (ref "C5") (pin "2") (pinfunction "2_2") (pintype "input"))
      (node (ref "U1") (pin "6") (pinfunction "PD1-OSC_OUT_6") (pintype "input"))
      (node (ref "X3") (pin "3") (pinfunction "3_3") (pintype "input"))
    )
    (net (code "35") (name "STM32_RDX") (class "Default")
      (node (ref "H2") (pin "1") (pinfunction "1_1") (pintype "input"))
      (node (ref "U1") (pin "31") (pinfunction "PA10_31") (pintype "input"))
    )
    (net (code "36") (name "STM32_TDX") (class "Default")
      (node (ref "H2") (pin "2") (pinfunction "2_2") (pintype "input"))
      (node (ref "U1") (pin "30") (pinfunction "PA9_30") (pintype "input"))
    )
    (net (code "37") (name "SWCLK") (class "Default")
      (node (ref "H1") (pin "3") (pinfunction "3_3") (pintype "input"))
      (node (ref "R13") (pin "1") (pinfunction "1_1") (pintype "input"))
      (node (ref "U1") (pin "37") (pinfunction "PA14_37") (pintype "input"))
    )
    (net (code "38") (name "SWDIO") (class "Default")
      (node (ref "H1") (pin "2") (pinfunction "2_2") (pintype "input"))
      (node (ref "R12") (pin "1") (pinfunction "1_1") (pintype "input"))
      (node (ref "U1") (pin "34") (pinfunction "PA13_34") (pintype "input"))
    )
    (net (code "39") (name "VCC-ZJ") (class "Default")
      (node (ref "C14") (pin "1") (pinfunction "1_1") (pintype "input"))
      (node (ref "C15") (pin "1") (pinfunction "1_1") (pintype "input"))
      (node (ref "P1") (pin "1") (pinfunction "1_1") (pintype "input"))
      (node (ref "R6") (pin "1") (pinfunction "1_1") (pintype "input"))
      (node (ref "U2") (pin "2") (pinfunction "K_2") (pintype "input"))
    )
    (net (code "40") (name "unconnected-(R7-Pad3)") (class "Default")
      (node (ref "R7") (pin "3") (pinfunction "3_3") (pintype "input+no_connect"))
    )
    (net (code "41") (name "unconnected-(SW1-Pad2)") (class "Default")
      (node (ref "SW1") (pin "2") (pinfunction "2_2") (pintype "input"))
    )
    (net (code "42") (name "unconnected-(SW1-Pad4)") (class "Default")
      (node (ref "SW1") (pin "4") (pinfunction "4_4") (pintype "input"))
    )
    (net (code "43") (name "unconnected-(SW2-Pad3)") (class "Default")
      (node (ref "SW2") (pin "3") (pinfunction "3_3") (pintype "input"))
    )
    (net (code "44") (name "unconnected-(SW4-Pad2)") (class "Default")
      (node (ref "SW4") (pin "2") (pinfunction "2_2") (pintype "input"))
    )
    (net (code "45") (name "unconnected-(SW4-Pad4)") (class "Default")
      (node (ref "SW4") (pin "4") (pinfunction "4_4") (pintype "input"))
    )
    (net (code "46") (name "unconnected-(U1-PA0-WKUP-Pad10)") (class "Default")
      (node (ref "U1") (pin "10") (pinfunction "PA0-WKUP_10") (pintype "input"))
    )
    (net (code "47") (name "unconnected-(U1-PA1-Pad11)") (class "Default")
      (node (ref "U1") (pin "11") (pinfunction "PA1_11") (pintype "input"))
    )
    (net (code "48") (name "unconnected-(U1-PA2-Pad12)") (class "Default")
      (node (ref "U1") (pin "12") (pinfunction "PA2_12") (pintype "input"))
    )
    (net (code "49") (name "unconnected-(U1-PA3-Pad13)") (class "Default")
      (node (ref "U1") (pin "13") (pinfunction "PA3_13") (pintype "input"))
    )
    (net (code "50") (name "unconnected-(U1-PA6-Pad16)") (class "Default")
      (node (ref "U1") (pin "16") (pinfunction "PA6_16") (pintype "input"))
    )
    (net (code "51") (name "unconnected-(U1-PA7-Pad17)") (class "Default")
      (node (ref "U1") (pin "17") (pinfunction "PA7_17") (pintype "input"))
    )
    (net (code "52") (name "unconnected-(U1-PA8-Pad29)") (class "Default")
      (node (ref "U1") (pin "29") (pinfunction "PA8_29") (pintype "input"))
    )
    (net (code "53") (name "unconnected-(U1-PA11-Pad32)") (class "Default")
      (node (ref "U1") (pin "32") (pinfunction "PA11_32") (pintype "input"))
    )
    (net (code "54") (name "unconnected-(U1-PA12-Pad33)") (class "Default")
      (node (ref "U1") (pin "33") (pinfunction "PA12_33") (pintype "input"))
    )
    (net (code "55") (name "unconnected-(U1-PA15-Pad38)") (class "Default")
      (node (ref "U1") (pin "38") (pinfunction "PA15_38") (pintype "input"))
    )
    (net (code "56") (name "unconnected-(U1-PB2-Pad20)") (class "Default")
      (node (ref "U1") (pin "20") (pinfunction "PB2_20") (pintype "input"))
    )
    (net (code "57") (name "unconnected-(U1-PB3-Pad39)") (class "Default")
      (node (ref "U1") (pin "39") (pinfunction "PB3_39") (pintype "input"))
    )
    (net (code "58") (name "unconnected-(U1-PB4-Pad40)") (class "Default")
      (node (ref "U1") (pin "40") (pinfunction "PB4_40") (pintype "input"))
    )
    (net (code "59") (name "unconnected-(U1-PB5-Pad41)") (class "Default")
      (node (ref "U1") (pin "41") (pinfunction "PB5_41") (pintype "input"))
    )
    (net (code "60") (name "unconnected-(U1-PB6-Pad42)") (class "Default")
      (node (ref "U1") (pin "42") (pinfunction "PB6_42") (pintype "input"))
    )
    (net (code "61") (name "unconnected-(U1-PB7-Pad43)") (class "Default")
      (node (ref "U1") (pin "43") (pinfunction "PB7_43") (pintype "input"))
    )
    (net (code "62") (name "unconnected-(U1-PB10-Pad21)") (class "Default")
      (node (ref "U1") (pin "21") (pinfunction "PB10_21") (pintype "input"))
    )
    (net (code "63") (name "unconnected-(U1-PB11-Pad22)") (class "Default")
      (node (ref "U1") (pin "22") (pinfunction "PB11_22") (pintype "input"))
    )
    (net (code "64") (name "unconnected-(U1-PB12-Pad25)") (class "Default")
      (node (ref "U1") (pin "25") (pinfunction "PB12_25") (pintype "input"))
    )
    (net (code "65") (name "unconnected-(U1-PB13-Pad26)") (class "Default")
      (node (ref "U1") (pin "26") (pinfunction "PB13_26") (pintype "input"))
    )
    (net (code "66") (name "unconnected-(U1-PB14-Pad27)") (class "Default")
      (node (ref "U1") (pin "27") (pinfunction "PB14_27") (pintype "input"))
    )
    (net (code "67") (name "unconnected-(U1-PB15-Pad28)") (class "Default")
      (node (ref "U1") (pin "28") (pinfunction "PB15_28") (pintype "input"))
    )
    (net (code "68") (name "unconnected-(U1-PC13-TAMPER-RTC-Pad2)") (class "Default")
      (node (ref "U1") (pin "2") (pinfunction "PC13-TAMPER-RTC_2") (pintype "input"))
    )
    (net (code "69") (name "unconnected-(U1-PC14-OSC32_IN-Pad3)") (class "Default")
      (node (ref "U1") (pin "3") (pinfunction "PC14-OSC32_IN_3") (pintype "input"))
    )
    (net (code "70") (name "unconnected-(U1-PC15-OSC32_OUT-Pad4)") (class "Default")
      (node (ref "U1") (pin "4") (pinfunction "PC15-OSC32_OUT_4") (pintype "input"))
    )
    (net (code "71") (name "unconnected-(U9-NC-Pad4)") (class "Default")
      (node (ref "U9") (pin "4") (pinfunction "NC_4") (pintype "input+no_connect"))
    )
  )
)
